# Sheet1.net
KiCad netlist of a schematic drawn in Altium Designer
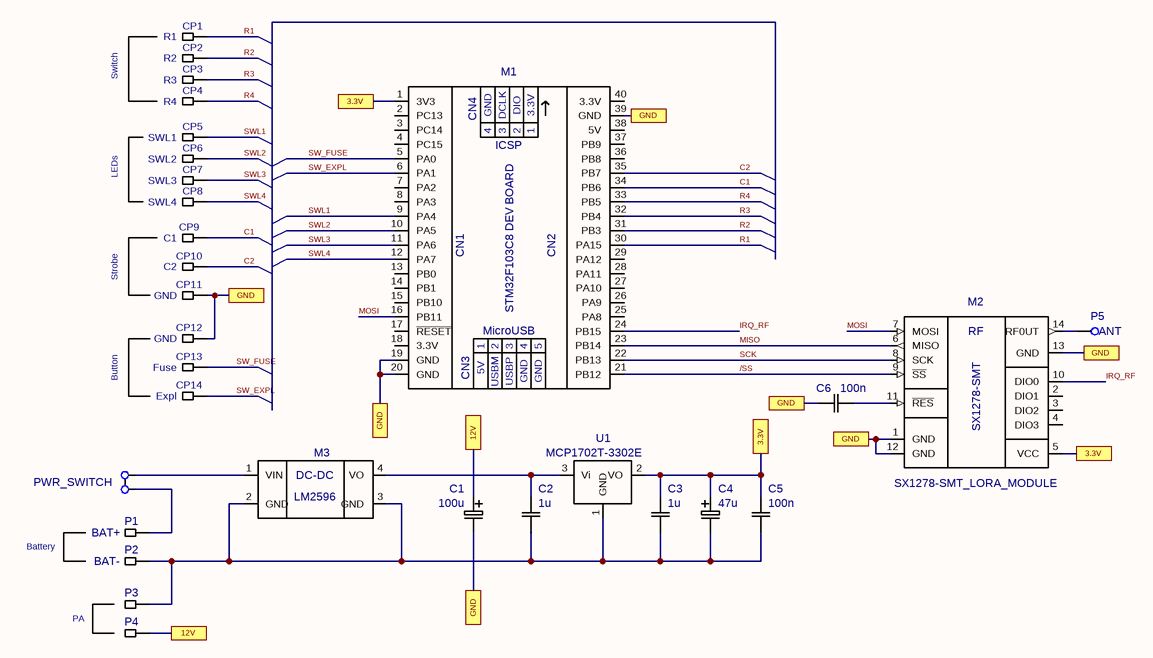
[diagram p0: Sheet1.SCHDOC]

(export (version "E")
  (design (tool "Eeschema 10.0.6"))
  (components
    (comp (ref "C1")
      (value "100u")
      (footprint "TAJHT1210")
      (description "TAJHT1210")
      (libsource (lib "*") (part "TAJHT1210"))
    )
    (comp (ref "C2")
      (value "1u")
      (footprint "C0805")
      (description "CAP_SMD_0805")
      (libsource (lib "*") (part "CAP_SMD_0805"))
    )
    (comp (ref "C3")
      (value "1u")
      (footprint "C0805")
      (description "CAP_SMD_0805")
      (libsource (lib "*") (part "CAP_SMD_0805"))
    )
    (comp (ref "C4")
      (value "47u")
      (footprint "TAJHT1210")
      (description "TAJHT1210")
      (libsource (lib "") (part "TAJHT1210_1"))
    )
    (comp (ref "C5")
      (value "100n")
      (footprint "C0805")
      (description "CAP_SMD_0805")
      (libsource (lib "*") (part "CAP_SMD_0805"))
    )
    (comp (ref "C6")
      (value "100n")
      (footprint "C0805")
      (description "CAP_SMD_0805")
      (libsource (lib "*") (part "CAP_SMD_0805"))
    )
    (comp (ref "CP1")
      (value "R1")
      (footprint "PAD_RRX60Y60D0T")
      (description "PAD_RRX60Y60D0T")
      (libsource (lib "*") (part "PAD_RRX60Y60D0T"))
    )
    (comp (ref "CP2")
      (value "R2")
      (footprint "PAD_RRX60Y60D0T")
      (description "PAD_RRX60Y60D0T")
      (libsource (lib "*") (part "PAD_RRX60Y60D0T"))
    )
    (comp (ref "CP3")
      (value "R3")
      (footprint "PAD_RRX60Y60D0T")
      (description "PAD_RRX60Y60D0T")
      (libsource (lib "*") (part "PAD_RRX60Y60D0T"))
    )
    (comp (ref "CP4")
      (value "R4")
      (footprint "PAD_RRX60Y60D0T")
      (description "PAD_RRX60Y60D0T")
      (libsource (lib "*") (part "PAD_RRX60Y60D0T"))
    )
    (comp (ref "CP5")
      (value "SWL1")
      (footprint "PAD_RRX60Y60D0T")
      (description "PAD_RRX60Y60D0T")
      (libsource (lib "*") (part "PAD_RRX60Y60D0T"))
    )
    (comp (ref "CP6")
      (value "SWL2")
      (footprint "PAD_RRX60Y60D0T")
      (description "PAD_RRX60Y60D0T")
      (libsource (lib "*") (part "PAD_RRX60Y60D0T"))
    )
    (comp (ref "CP7")
      (value "SWL3")
      (footprint "PAD_RRX60Y60D0T")
      (description "PAD_RRX60Y60D0T")
      (libsource (lib "*") (part "PAD_RRX60Y60D0T"))
    )
    (comp (ref "CP8")
      (value "SWL4")
      (footprint "PAD_RRX60Y60D0T")
      (description "PAD_RRX60Y60D0T")
      (libsource (lib "*") (part "PAD_RRX60Y60D0T"))
    )
    (comp (ref "CP9")
      (value "C1")
      (footprint "PAD_RRX60Y60D0T")
      (description "PAD_RRX60Y60D0T")
      (libsource (lib "*") (part "PAD_RRX60Y60D0T"))
    )
    (comp (ref "CP10")
      (value "C2")
      (footprint "PAD_RRX60Y60D0T")
      (description "PAD_RRX60Y60D0T")
      (libsource (lib "*") (part "PAD_RRX60Y60D0T"))
    )
    (comp (ref "CP11")
      (value "GND")
      (footprint "PAD_RRX60Y60D0T")
      (description "PAD_RRX60Y60D0T")
      (libsource (lib "*") (part "PAD_RRX60Y60D0T"))
    )
    (comp (ref "CP12")
      (value "GND")
      (footprint "PAD_RRX60Y60D0T")
      (description "PAD_RRX60Y60D0T")
      (libsource (lib "*") (part "PAD_RRX60Y60D0T"))
    )
    (comp (ref "CP13")
      (value "Fuse")
      (footprint "PAD_RRX60Y60D0T")
      (description "PAD_RRX60Y60D0T")
      (libsource (lib "*") (part "PAD_RRX60Y60D0T"))
    )
    (comp (ref "CP14")
      (value "Expl")
      (footprint "PAD_RRX60Y60D0T")
      (description "PAD_RRX60Y60D0T")
      (libsource (lib "*") (part "PAD_RRX60Y60D0T"))
    )
    (comp (ref "M1")
      (value "STM32F103_DEV_BOARD")
      (footprint "STM32F103C8_DEV_BOARD")
      (libsource (lib "*") (part "STM32F103_DEV_BOARD"))
    )
    (comp (ref "M2")
      (value "SX1278-SMT_LORA_MODULE")
      (footprint "SX1278-SMT_MODULE")
      (description "Radiomodule LoRa. 433MHz 20mW max.")
      (libsource (lib "*") (part "SX1278-SMT_LORA_MODULE"))
    )
    (comp (ref "M3")
      (value "LM2596_DC-DC")
      (footprint "LM2596_DC-DC")
      (description "Converter DC-DC Module")
      (libsource (lib "*") (part "LM2596_DC-DC"))
    )
    (comp (ref "P1")
      (value "BAT+")
      (footprint "PAD_RRX60Y120D0T")
      (description "PAD_RRX60Y120D0T")
      (libsource (lib "*") (part "PAD_RRX60Y120D0T"))
    )
    (comp (ref "P2")
      (value "BAT-")
      (footprint "PAD_RRX60Y120D0T")
      (description "PAD_RRX60Y120D0T")
      (libsource (lib "*") (part "PAD_RRX60Y120D0T"))
    )
    (comp (ref "P3")
      (value "PAD_RRX60Y120D0T")
      (footprint "PAD_RRX60Y120D0T")
      (libsource (lib "*") (part "PAD_RRX60Y120D0T"))
    )
    (comp (ref "P4")
      (value "PAD_RRX60Y120D0T")
      (footprint "PAD_RRX60Y120D0T")
      (libsource (lib "*") (part "PAD_RRX60Y120D0T"))
    )
    (comp (ref "P5")
      (value "ANT")
      (footprint "PAD_EX32Y32AD20")
      (description "PAD_EX32Y32D20")
      (libsource (lib "*") (part "PAD_EX32Y32D20"))
    )
    (comp (ref "PWR_SWITCH")
      (value "2P:EX60Y60D0T-CD100")
      (footprint "2P:EX60Y60D0T-CD100")
      (libsource (lib "*") (part "2P{colon}EX60Y60D0T-CD100"))
    )
    (comp (ref "U1")
      (value "MCP1702T-3302E")
      (footprint "SOT23A")
      (description "Voltage Stabilizer 3.3V 100mA Iq=2uA")
      (libsource (lib "*") (part "MCP1702T-3302E"))
    )
  )
  (nets
    (net (code "1") (name "/3.3V") (class "Default")
      (node (ref "C3") (pin "2") (pinfunction "B_2") (pintype "passive"))
      (node (ref "C4") (pin "1") (pintype "passive"))
      (node (ref "C5") (pin "2") (pinfunction "B_2") (pintype "passive"))
      (node (ref "M1") (pin "1") (pinfunction "3V3_1") (pintype "passive"))
      (node (ref "M2") (pin "5") (pinfunction "VCC_5") (pintype "power_in"))
      (node (ref "U1") (pin "2") (pinfunction "VO_2") (pintype "passive"))
    )
    (net (code "2") (name "/12V") (class "Default")
      (node (ref "C1") (pin "1") (pintype "passive"))
      (node (ref "P4") (pin "1") (pintype "passive"))
    )
    (net (code "3") (name "/C1") (class "Default")
      (node (ref "CP9") (pin "1") (pintype "passive"))
      (node (ref "M1") (pin "34") (pinfunction "PB6_34") (pintype "passive"))
    )
    (net (code "4") (name "/C2") (class "Default")
      (node (ref "CP10") (pin "1") (pintype "passive"))
      (node (ref "M1") (pin "35") (pinfunction "PB7_35") (pintype "passive"))
    )
    (net (code "5") (name "/GND") (class "Default")
      (node (ref "C1") (pin "2") (pintype "passive"))
      (node (ref "C6") (pin "1") (pinfunction "A_1") (pintype "passive"))
      (node (ref "CP11") (pin "1") (pintype "passive"))
      (node (ref "CP12") (pin "1") (pintype "passive"))
      (node (ref "M1") (pin "19") (pinfunction "GND_19") (pintype "passive"))
      (node (ref "M1") (pin "20") (pinfunction "GND_20") (pintype "passive"))
      (node (ref "M1") (pin "39") (pinfunction "GND_39") (pintype "passive"))
      (node (ref "M2") (pin "1") (pinfunction "GND_1") (pintype "power_in"))
      (node (ref "M2") (pin "12") (pinfunction "GND_12") (pintype "power_in"))
      (node (ref "M2") (pin "13") (pinfunction "GND_13") (pintype "power_in"))
    )
    (net (code "6") (name "/IRQ_RF") (class "Default")
      (node (ref "M1") (pin "24") (pinfunction "PB15_24") (pintype "passive"))
      (node (ref "M2") (pin "10") (pinfunction "DIO0_10") (pintype "bidirectional"))
    )
    (net (code "7") (name "/MISO") (class "Default")
      (node (ref "M1") (pin "23") (pinfunction "PB14_23") (pintype "passive"))
      (node (ref "M2") (pin "6") (pinfunction "MISO_6") (pintype "output"))
    )
    (net (code "8") (name "/MOSI") (class "Default")
      (node (ref "M1") (pin "16") (pinfunction "PB11_16") (pintype "passive"))
      (node (ref "M2") (pin "7") (pinfunction "MOSI_7") (pintype "input"))
    )
    (net (code "9") (name "/R1") (class "Default")
      (node (ref "CP1") (pin "1") (pintype "passive"))
      (node (ref "M1") (pin "30") (pinfunction "PA15_30") (pintype "passive"))
    )
    (net (code "10") (name "/R2") (class "Default")
      (node (ref "CP2") (pin "1") (pintype "passive"))
      (node (ref "M1") (pin "31") (pinfunction "PB3_31") (pintype "passive"))
    )
    (net (code "11") (name "/R3") (class "Default")
      (node (ref "CP3") (pin "1") (pintype "passive"))
      (node (ref "M1") (pin "32") (pinfunction "PB4_32") (pintype "passive"))
    )
    (net (code "12") (name "/R4") (class "Default")
      (node (ref "CP4") (pin "1") (pintype "passive"))
      (node (ref "M1") (pin "33") (pinfunction "PB5_33") (pintype "passive"))
    )
    (net (code "13") (name "/SCK") (class "Default")
      (node (ref "M1") (pin "22") (pinfunction "PB13_22") (pintype "passive"))
      (node (ref "M2") (pin "8") (pinfunction "SCK_8") (pintype "input"))
    )
    (net (code "14") (name "/SWL1") (class "Default")
      (node (ref "CP5") (pin "1") (pintype "passive"))
      (node (ref "M1") (pin "9") (pinfunction "PA4_9") (pintype "passive"))
    )
    (net (code "15") (name "/SWL2") (class "Default")
      (node (ref "CP6") (pin "1") (pintype "passive"))
      (node (ref "M1") (pin "10") (pinfunction "PA5_10") (pintype "passive"))
    )
    (net (code "16") (name "/SWL3") (class "Default")
      (node (ref "CP7") (pin "1") (pintype "passive"))
      (node (ref "M1") (pin "11") (pinfunction "PA6_11") (pintype "passive"))
    )
    (net (code "17") (name "/SWL4") (class "Default")
      (node (ref "CP8") (pin "1") (pintype "passive"))
      (node (ref "M1") (pin "12") (pinfunction "PA7_12") (pintype "passive"))
    )
    (net (code "18") (name "/SW_EXPL") (class "Default")
      (node (ref "CP14") (pin "1") (pintype "passive"))
      (node (ref "M1") (pin "6") (pinfunction "PA1_6") (pintype "passive"))
    )
    (net (code "19") (name "/SW_FUSE") (class "Default")
      (node (ref "CP13") (pin "1") (pintype "passive"))
      (node (ref "M1") (pin "5") (pinfunction "PA0_5") (pintype "passive"))
    )
    (net (code "20") (name "/{slash}SS") (class "Default")
      (node (ref "M1") (pin "21") (pinfunction "PB12_21") (pintype "passive"))
      (node (ref "M2") (pin "9") (pinfunction "~{SS}_9") (pintype "input"))
    )
    (net (code "21") (name "Net-(C2-A)") (class "Default")
      (node (ref "C2") (pin "1") (pinfunction "A_1") (pintype "passive"))
      (node (ref "C3") (pin "1") (pinfunction "A_1") (pintype "passive"))
      (node (ref "C4") (pin "2") (pintype "passive"))
      (node (ref "C5") (pin "1") (pinfunction "A_1") (pintype "passive"))
      (node (ref "M3") (pin "2") (pinfunction "GND_2") (pintype "passive"))
      (node (ref "M3") (pin "3") (pinfunction "GND_3") (pintype "passive"))
      (node (ref "P2") (pin "1") (pintype "passive"))
      (node (ref "P3") (pin "1") (pintype "passive"))
      (node (ref "U1") (pin "1") (pinfunction "GND_1") (pintype "passive"))
    )
    (net (code "22") (name "Net-(C2-B)") (class "Default")
      (node (ref "C2") (pin "2") (pinfunction "B_2") (pintype "passive"))
      (node (ref "M3") (pin "4") (pinfunction "VO_4") (pintype "passive"))
      (node (ref "U1") (pin "3") (pinfunction "Vi_3") (pintype "passive"))
    )
    (net (code "23") (name "Net-(C6-B)") (class "Default")
      (node (ref "C6") (pin "2") (pinfunction "B_2") (pintype "passive"))
      (node (ref "M2") (pin "11") (pinfunction "~{RES}_11") (pintype "input"))
    )
    (net (code "24") (name "Net-(M2-RF0UT)") (class "Default")
      (node (ref "M2") (pin "14") (pinfunction "RF0UT_14") (pintype "output"))
      (node (ref "P5") (pin "1") (pintype "passive"))
    )
    (net (code "25") (name "Net-(M3-VIN)") (class "Default")
      (node (ref "M3") (pin "1") (pinfunction "VIN_1") (pintype "passive"))
      (node (ref "PWR_SWITCH") (pin "1") (pintype "passive"))
    )
    (net (code "26") (name "Net-(P1-Pad1)") (class "Default")
      (node (ref "P1") (pin "1") (pintype "passive"))
      (node (ref "PWR_SWITCH") (pin "2") (pintype "passive"))
    )
    (net (code "27") (name "unconnected-(M1-3.3V-Pad18)") (class "Default")
      (node (ref "M1") (pin "18") (pinfunction "3.3V_18") (pintype "passive"))
    )
    (net (code "28") (name "unconnected-(M1-3.3V-Pad40)") (class "Default")
      (node (ref "M1") (pin "40") (pinfunction "3.3V_40") (pintype "passive"))
    )
    (net (code "29") (name "unconnected-(M1-5V-Pad38)") (class "Default")
      (node (ref "M1") (pin "38") (pinfunction "5V_38") (pintype "passive"))
    )
    (net (code "30") (name "unconnected-(M1-PA2-Pad7)") (class "Default")
      (node (ref "M1") (pin "7") (pinfunction "PA2_7") (pintype "passive"))
    )
    (net (code "31") (name "unconnected-(M1-PA3-Pad8)") (class "Default")
      (node (ref "M1") (pin "8") (pinfunction "PA3_8") (pintype "passive"))
    )
    (net (code "32") (name "unconnected-(M1-PA8-Pad25)") (class "Default")
      (node (ref "M1") (pin "25") (pinfunction "PA8_25") (pintype "passive"))
    )
    (net (code "33") (name "unconnected-(M1-PA9-Pad26)") (class "Default")
      (node (ref "M1") (pin "26") (pinfunction "PA9_26") (pintype "passive"))
    )
    (net (code "34") (name "unconnected-(M1-PA10-Pad27)") (class "Default")
      (node (ref "M1") (pin "27") (pinfunction "PA10_27") (pintype "passive"))
    )
    (net (code "35") (name "unconnected-(M1-PA11-Pad28)") (class "Default")
      (node (ref "M1") (pin "28") (pinfunction "PA11_28") (pintype "passive"))
    )
    (net (code "36") (name "unconnected-(M1-PA12-Pad29)") (class "Default")
      (node (ref "M1") (pin "29") (pinfunction "PA12_29") (pintype "passive"))
    )
    (net (code "37") (name "unconnected-(M1-PB0-Pad13)") (class "Default")
      (node (ref "M1") (pin "13") (pinfunction "PB0_13") (pintype "passive"))
    )
    (net (code "38") (name "unconnected-(M1-PB1-Pad14)") (class "Default")
      (node (ref "M1") (pin "14") (pinfunction "PB1_14") (pintype "passive"))
    )
    (net (code "39") (name "unconnected-(M1-PB8-Pad36)") (class "Default")
      (node (ref "M1") (pin "36") (pinfunction "PB8_36") (pintype "passive"))
    )
    (net (code "40") (name "unconnected-(M1-PB9-Pad37)") (class "Default")
      (node (ref "M1") (pin "37") (pinfunction "PB9_37") (pintype "passive"))
    )
    (net (code "41") (name "unconnected-(M1-PB10-Pad15)") (class "Default")
      (node (ref "M1") (pin "15") (pinfunction "PB10_15") (pintype "passive"))
    )
    (net (code "42") (name "unconnected-(M1-PC13-Pad2)") (class "Default")
      (node (ref "M1") (pin "2") (pinfunction "PC13_2") (pintype "passive"))
    )
    (net (code "43") (name "unconnected-(M1-PC14-Pad3)") (class "Default")
      (node (ref "M1") (pin "3") (pinfunction "PC14_3") (pintype "passive"))
    )
    (net (code "44") (name "unconnected-(M1-PC15-Pad4)") (class "Default")
      (node (ref "M1") (pin "4") (pinfunction "PC15_4") (pintype "passive"))
    )
    (net (code "45") (name "unconnected-(M1-~{RESET}-Pad17)") (class "Default")
      (node (ref "M1") (pin "17") (pinfunction "~{RESET}_17") (pintype "passive"))
    )
    (net (code "46") (name "unconnected-(M2-DIO1-Pad2)") (class "Default")
      (node (ref "M2") (pin "2") (pinfunction "DIO1_2") (pintype "bidirectional"))
    )
    (net (code "47") (name "unconnected-(M2-DIO2-Pad3)") (class "Default")
      (node (ref "M2") (pin "3") (pinfunction "DIO2_3") (pintype "bidirectional"))
    )
    (net (code "48") (name "unconnected-(M2-DIO3-Pad4)") (class "Default")
      (node (ref "M2") (pin "4") (pinfunction "DIO3_4") (pintype "bidirectional"))
    )
  )
)
